# MAXREFDES117.net
KiCad netlist of a schematic drawn in Altium Designer
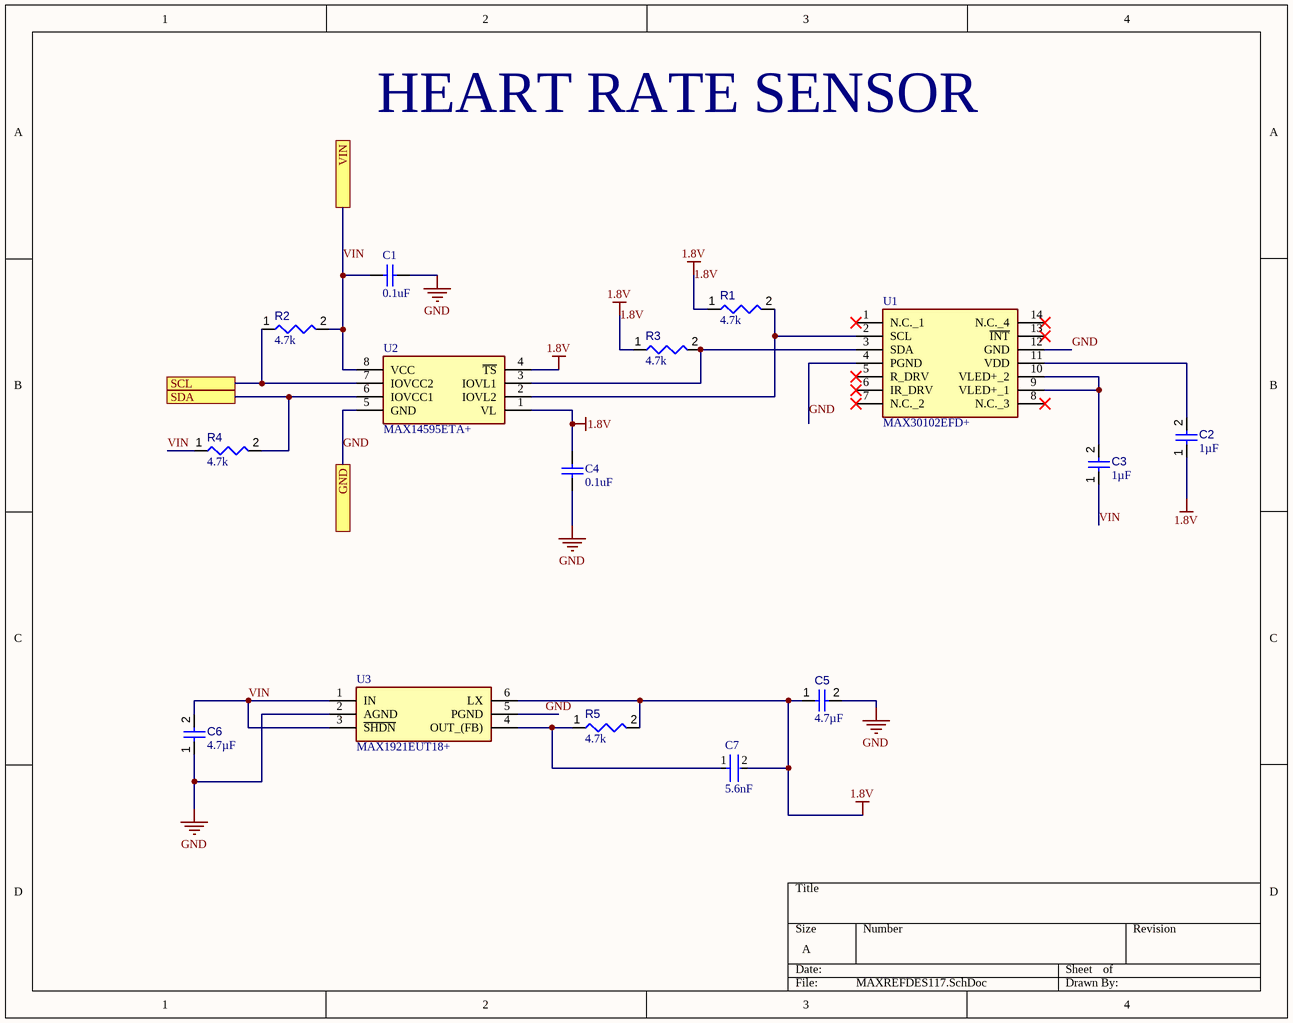
[diagram p0: MAXREFDES117.SchDoc]

(export (version "E")
  (design (tool "Eeschema 10.0.6"))
  (components
    (comp (ref "C1")
      (value "0.1uF")
      (footprint "CAPC1608X90X35ML10T15")
      (description "Chip Capacitor, 0.1 uF, +/- 10%, 50 V, -55 to 125 degC, 0603 (1608 Metric), RoHS, Tape and Reel")
      (fields (field (name "TOLERANCE") "10%") (field (name "VOLTAGE") "50V"))
      (libsource (lib "Altium Content Vault") (part "CAP-NP-2"))
    )
    (comp (ref "C2")
      (value "1µF")
      (footprint "CAPC0402(1005)60_L")
      (description "Chip Capacitor, 1µF +/-20%, 10V, 0402, Thickness 0.6 mm")
      (fields (field (name "TOLERANCE") "10%") (field (name "Comment") "Capacitor 1µF +/-20% 10V 0402"))
      (libsource (lib "JCGada") (part "CAP-NP-2"))
    )
    (comp (ref "C3")
      (value "1µF")
      (footprint "CAPC0402(1005)60_L")
      (description "Chip Capacitor, 1µF +/-20%, 10V, 0402, Thickness 0.6 mm")
      (fields (field (name "TOLERANCE") "10%") (field (name "Comment") "Capacitor 1µF +/-20% 10V 0402"))
      (libsource (lib "JCGada") (part "CAP-NP-2"))
    )
    (comp (ref "C4")
      (value "0.1uF")
      (footprint "CAPC1608X90X35ML10T15")
      (description "Chip Capacitor, 0.1 uF, +/- 10%, 50 V, -55 to 125 degC, 0603 (1608 Metric), RoHS, Tape and Reel")
      (fields (field (name "TOLERANCE") "10%") (field (name "VOLTAGE") "50V"))
      (libsource (lib "Altium Content Vault") (part "CAP-NP-2"))
    )
    (comp (ref "C5")
      (value "4.7µF")
      (footprint "CAPC0603(1608)100_L")
      (description "Chip Capacitor, 4.7µF +/-20%, 10V, 0603, Thickness 1 mm")
      (fields (field (name "TOLERANCE") "10%") (field (name "Comment") "Capacitor 4.7µF +/-20% 10V 0603"))
      (libsource (lib "JCGada") (part "CAP-NP-2"))
    )
    (comp (ref "C6")
      (value "4.7µF")
      (footprint "CAPC0603(1608)100_L")
      (description "Chip Capacitor, 4.7µF +/-20%, 10V, 0603, Thickness 1 mm")
      (fields (field (name "TOLERANCE") "10%") (field (name "Comment") "Capacitor 4.7µF +/-20% 10V 0603"))
      (libsource (lib "JCGada") (part "CAP-NP-2"))
    )
    (comp (ref "C7")
      (value "5.6nF")
      (footprint "FP-C0603C-CF-MFG")
      (description "CAP CER 5600PF 50V NP0 0603")
      (fields
        (field (name "TOLERANCE") "0.05")
        (field (name "OCTOPART") "https://octopart.com/c0603c562j5gactu-kemet-13174209")
      )
      (libsource (lib "Altium Content Vault") (part "b4654b650e69147ec39a6b967a45e02"))
    )
    (comp (ref "R1")
      (value "4.7k")
      (footprint "RESC0402(1005)_L")
      (description "4K7 0.063W 1% 0402 (1005 Metric)  SMD")
      (fields (field (name "TOLERANCE") "1%") (field (name "POWER") "63mW"))
      (libsource (lib "JCGada") (part "4D7KR2F"))
    )
    (comp (ref "R2")
      (value "4.7k")
      (footprint "RESC0402(1005)_L")
      (description "4K7 0.063W 1% 0402 (1005 Metric)  SMD")
      (fields (field (name "TOLERANCE") "1%") (field (name "POWER") "63mW"))
      (libsource (lib "JCGada") (part "4D7KR2F"))
    )
    (comp (ref "R3")
      (value "4.7k")
      (footprint "RESC0402(1005)_L")
      (description "4K7 0.063W 1% 0402 (1005 Metric)  SMD")
      (fields (field (name "TOLERANCE") "1%") (field (name "POWER") "63mW"))
      (libsource (lib "JCGada") (part "4D7KR2F"))
    )
    (comp (ref "R4")
      (value "4.7k")
      (footprint "RESC0402(1005)_L")
      (description "4K7 0.063W 1% 0402 (1005 Metric)  SMD")
      (fields (field (name "TOLERANCE") "1%") (field (name "POWER") "63mW"))
      (libsource (lib "JCGada") (part "4D7KR2F"))
    )
    (comp (ref "R5")
      (value "4.7k")
      (footprint "RESC0402(1005)_L")
      (description "4K7 0.063W 1% 0402 (1005 Metric)  SMD")
      (fields (field (name "TOLERANCE") "1%") (field (name "POWER") "63mW"))
      (libsource (lib "JCGada") (part "4D7KR2F"))
    )
    (comp (ref "U1")
      (value "MAX30102EFD+")
      (footprint "PcbLib1:14-LEAD-OESIP")
      (description "Integrated Circuit")
      (fields (field (name "MOUSER PART NUMBER") "700-MAX30102EFD+"))
      (libsource (lib "*") (part "MAX30102EFD+"))
    )
    (comp (ref "U2")
      (value "MAX14595ETA+")
      (footprint "PcbLib1:MAX14595ETA")
      (description "Integrated Circuit")
      (fields (field (name "MOUSER PART NUMBER") "700-MAX14595ETA+"))
      (libsource (lib "*") (part "MAX14595ETA+"))
    )
    (comp (ref "U3")
      (value "MAX1921EUT18+")
      (footprint "PcbLib1:SOT95P280X145-6N")
      (description "Integrated Circuit")
      (libsource (lib "*") (part "MAX1921EUT18+"))
    )
  )
  (nets
    (net (code "1") (name "/SCL") (class "Default")
      (node (ref "R2") (pin "1") (pinfunction "1_1") (pintype "passive"))
      (node (ref "U2") (pin "7") (pinfunction "IOVCC2_7") (pintype "passive"))
    )
    (net (code "2") (name "/SDA") (class "Default")
      (node (ref "R4") (pin "2") (pinfunction "2_2") (pintype "passive"))
      (node (ref "U2") (pin "6") (pinfunction "IOVCC1_6") (pintype "passive"))
    )
    (net (code "3") (name "/VIN") (class "Default")
      (node (ref "C1") (pin "2") (pinfunction "2_2") (pintype "passive"))
      (node (ref "C3") (pin "1") (pinfunction "1_1") (pintype "passive"))
      (node (ref "C6") (pin "2") (pinfunction "2_2") (pintype "passive"))
      (node (ref "R2") (pin "2") (pinfunction "2_2") (pintype "passive"))
      (node (ref "R4") (pin "1") (pinfunction "1_1") (pintype "passive"))
      (node (ref "U2") (pin "8") (pinfunction "VCC_8") (pintype "passive"))
      (node (ref "U3") (pin "1") (pinfunction "IN_1") (pintype "passive"))
      (node (ref "U3") (pin "3") (pinfunction "~{SHDN}_3") (pintype "passive"))
    )
    (net (code "4") (name "1.8V") (class "Default")
      (node (ref "C2") (pin "1") (pinfunction "1_1") (pintype "passive"))
      (node (ref "C4") (pin "2") (pinfunction "2_2") (pintype "passive"))
      (node (ref "C5") (pin "1") (pinfunction "1_1") (pintype "passive"))
      (node (ref "C7") (pin "2") (pinfunction "2_2") (pintype "passive"))
      (node (ref "R1") (pin "1") (pinfunction "1_1") (pintype "passive"))
      (node (ref "R3") (pin "1") (pinfunction "1_1") (pintype "passive"))
      (node (ref "R5") (pin "2") (pinfunction "2_2") (pintype "passive"))
      (node (ref "U2") (pin "1") (pinfunction "VL_1") (pintype "passive"))
      (node (ref "U2") (pin "4") (pinfunction "~{TS}_4") (pintype "passive"))
      (node (ref "U3") (pin "6") (pinfunction "LX_6") (pintype "passive"))
    )
    (net (code "5") (name "GND") (class "Default")
      (node (ref "C1") (pin "1") (pinfunction "1_1") (pintype "passive"))
      (node (ref "C4") (pin "1") (pinfunction "1_1") (pintype "passive"))
      (node (ref "C5") (pin "2") (pinfunction "2_2") (pintype "passive"))
      (node (ref "C6") (pin "1") (pinfunction "1_1") (pintype "passive"))
      (node (ref "U1") (pin "12") (pinfunction "GND_12") (pintype "passive"))
      (node (ref "U1") (pin "4") (pinfunction "PGND_4") (pintype "passive"))
      (node (ref "U2") (pin "5") (pinfunction "GND_5") (pintype "passive"))
      (node (ref "U3") (pin "2") (pinfunction "AGND_2") (pintype "passive"))
      (node (ref "U3") (pin "5") (pinfunction "PGND_5") (pintype "passive"))
    )
    (net (code "6") (name "Net-(U1-SCL)") (class "Default")
      (node (ref "R1") (pin "2") (pinfunction "2_2") (pintype "passive"))
      (node (ref "U1") (pin "2") (pinfunction "SCL_2") (pintype "passive"))
      (node (ref "U2") (pin "2") (pinfunction "IOVL2_2") (pintype "passive"))
    )
    (net (code "7") (name "Net-(U1-SDA)") (class "Default")
      (node (ref "R3") (pin "2") (pinfunction "2_2") (pintype "passive"))
      (node (ref "U1") (pin "3") (pinfunction "SDA_3") (pintype "passive"))
      (node (ref "U2") (pin "3") (pinfunction "IOVL1_3") (pintype "passive"))
    )
    (net (code "8") (name "Net-(U1-VDD)") (class "Default")
      (node (ref "C2") (pin "2") (pinfunction "2_2") (pintype "passive"))
      (node (ref "U1") (pin "11") (pinfunction "VDD_11") (pintype "passive"))
    )
    (net (code "9") (name "Net-(U1-VLED+_1)") (class "Default")
      (node (ref "C3") (pin "2") (pinfunction "2_2") (pintype "passive"))
      (node (ref "U1") (pin "10") (pinfunction "VLED+_2_10") (pintype "passive"))
      (node (ref "U1") (pin "9") (pinfunction "VLED+_1_9") (pintype "passive"))
    )
    (net (code "10") (name "Net-(U3-OUT_(FB))") (class "Default")
      (node (ref "C7") (pin "1") (pinfunction "1_1") (pintype "passive"))
      (node (ref "R5") (pin "1") (pinfunction "1_1") (pintype "passive"))
      (node (ref "U3") (pin "4") (pinfunction "OUT_(FB)_4") (pintype "passive"))
    )
    (net (code "11") (name "unconnected-(U1-IR_DRV-Pad6)") (class "Default")
      (node (ref "U1") (pin "6") (pinfunction "IR_DRV_6") (pintype "passive+no_connect"))
    )
    (net (code "12") (name "unconnected-(U1-N.C._1-Pad1)") (class "Default")
      (node (ref "U1") (pin "1") (pinfunction "N.C._1_1") (pintype "passive+no_connect"))
    )
    (net (code "13") (name "unconnected-(U1-N.C._2-Pad7)") (class "Default")
      (node (ref "U1") (pin "7") (pinfunction "N.C._2_7") (pintype "passive+no_connect"))
    )
    (net (code "14") (name "unconnected-(U1-N.C._3-Pad8)") (class "Default")
      (node (ref "U1") (pin "8") (pinfunction "N.C._3_8") (pintype "passive+no_connect"))
    )
    (net (code "15") (name "unconnected-(U1-N.C._4-Pad14)") (class "Default")
      (node (ref "U1") (pin "14") (pinfunction "N.C._4_14") (pintype "passive+no_connect"))
    )
    (net (code "16") (name "unconnected-(U1-R_DRV-Pad5)") (class "Default")
      (node (ref "U1") (pin "5") (pinfunction "R_DRV_5") (pintype "passive+no_connect"))
    )
    (net (code "17") (name "unconnected-(U1-~{INT}-Pad13)") (class "Default")
      (node (ref "U1") (pin "13") (pinfunction "~{INT}_13") (pintype "passive+no_connect"))
    )
  )
)
